# IoT_Shield_v1_2.net
KiCad netlist of a schematic drawn in EAGLE
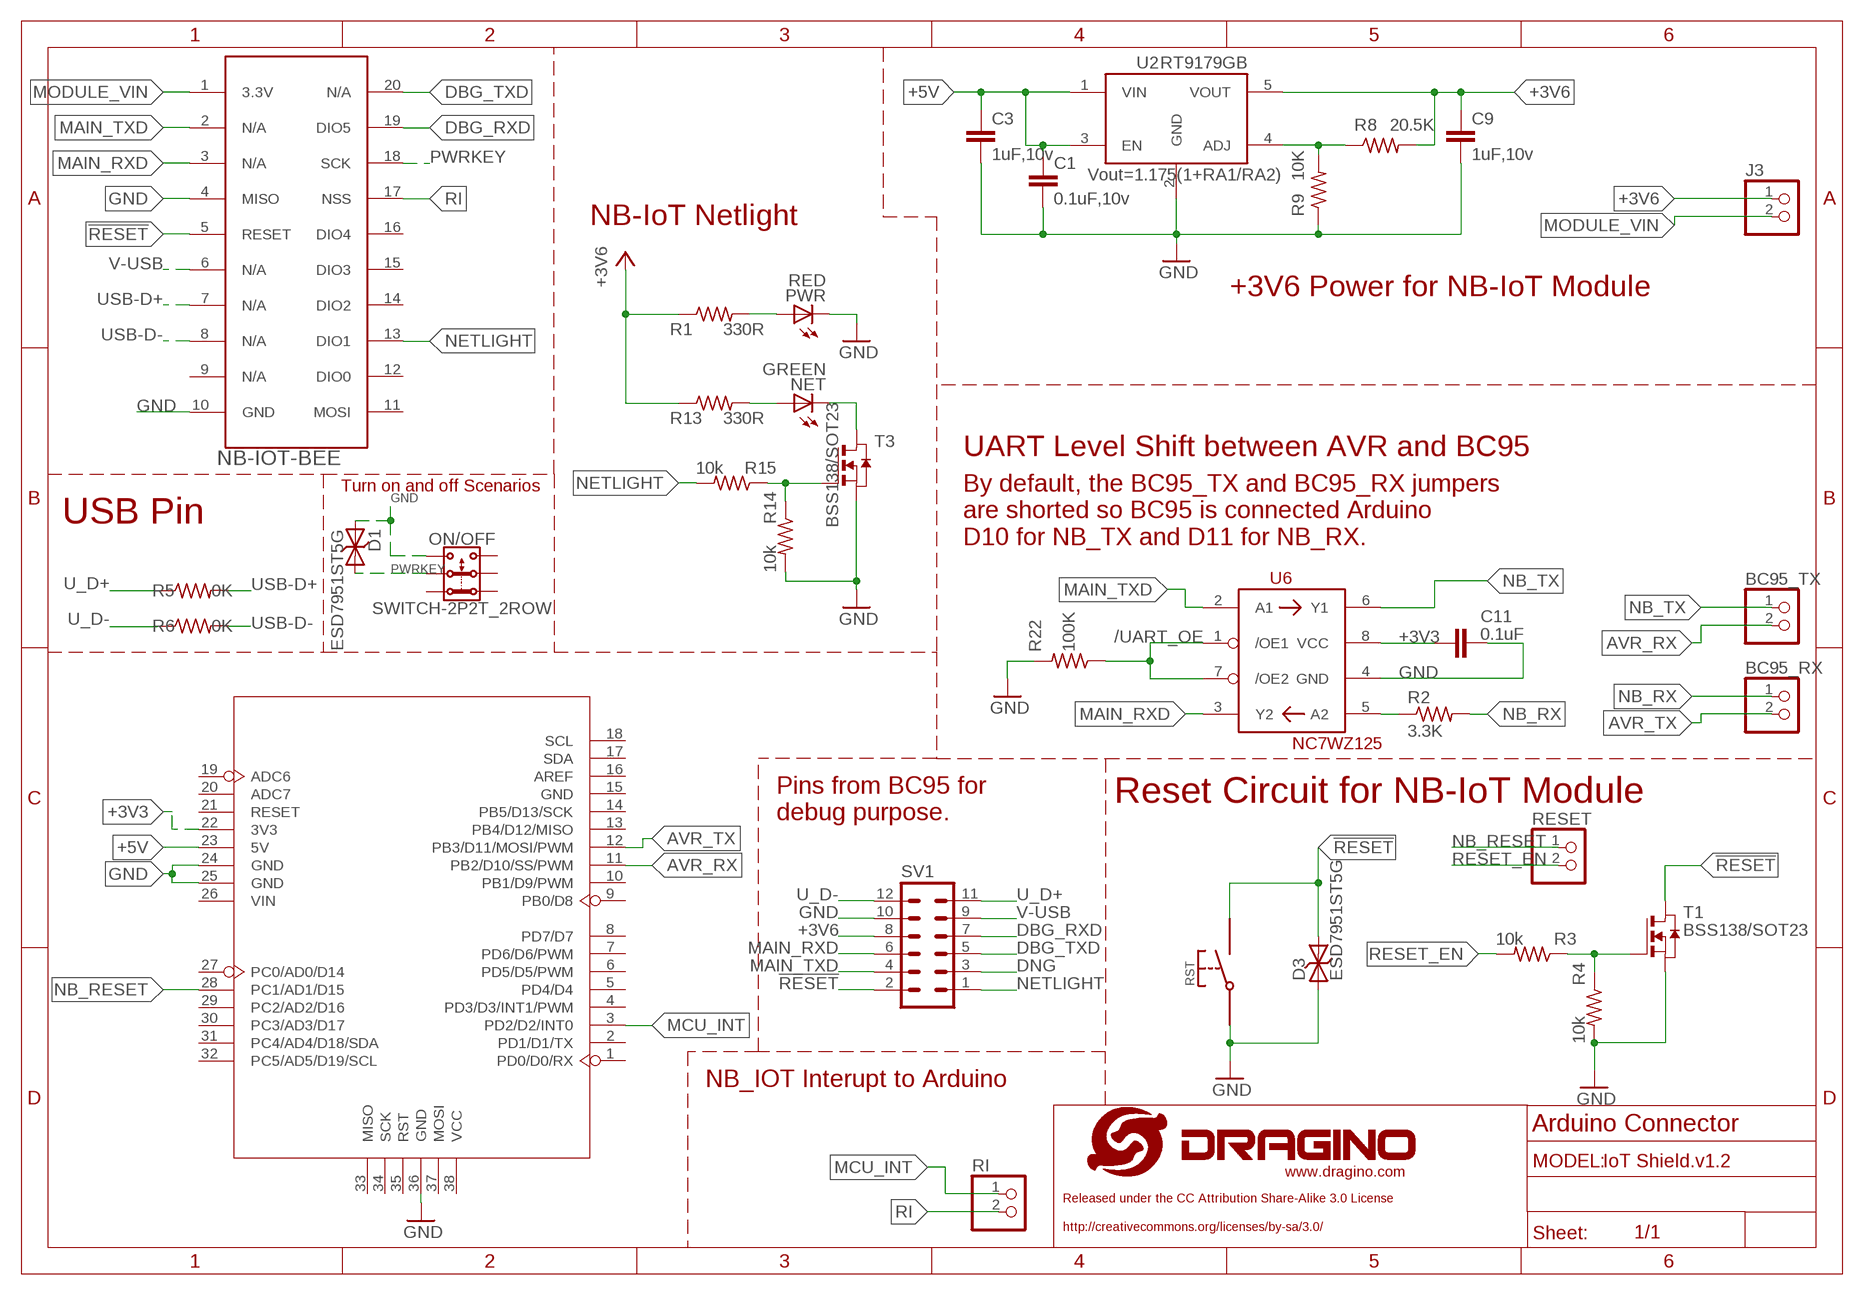
[diagram p0: schematic, sheet 1]

(export (version "E")
  (design (tool "Eeschema 10.0.6"))
  (components
    (comp (ref "BC95_RX")
      (value "PINHD-1X2")
      (footprint "eagle-import:1X02")
      (libsource (lib "eagle-import") (part "PINHD-1X2"))
    )
    (comp (ref "BC95_TX")
      (value "PINHD-1X2")
      (footprint "eagle-import:1X02")
      (libsource (lib "eagle-import") (part "PINHD-1X2"))
    )
    (comp (ref "C1")
      (value "0.1uF,10v")
      (footprint "eagle-import:C0402")
      (libsource (lib "eagle-import") (part "C-EUC0402"))
    )
    (comp (ref "C3")
      (value "1uF,10v")
      (footprint "eagle-import:C0402")
      (libsource (lib "eagle-import") (part "C-EUC0402"))
    )
    (comp (ref "C9")
      (value "1uF,10v")
      (footprint "eagle-import:C0402")
      (libsource (lib "eagle-import") (part "C-EUC0402"))
    )
    (comp (ref "C11")
      (value "0.1uF")
      (footprint "eagle-import:C0402")
      (libsource (lib "eagle-import") (part "C-EUC0402"))
    )
    (comp (ref "D1")
      (value "ESD7951ST5G")
      (footprint "eagle-import:SOD−923")
      (libsource (lib "eagle-import") (part "TVSSOD−923"))
    )
    (comp (ref "D3")
      (value "ESD7951ST5G")
      (footprint "eagle-import:SOD−923")
      (libsource (lib "eagle-import") (part "TVSSOD−923"))
    )
    (comp (ref "IOT-BEE")
      (value "NB-IOT-BEE")
      (footprint "eagle-import:LORA")
      (libsource (lib "eagle-import") (part "LORAHAT_S"))
    )
    (comp (ref "J3")
      (value "PINHD-1X2")
      (footprint "eagle-import:1X02")
      (libsource (lib "eagle-import") (part "PINHD-1X2"))
    )
    (comp (ref "NET")
      (value "GREEN")
      (footprint "eagle-import:CHIP-LED0603")
      (libsource (lib "eagle-import") (part "LEDCHIP-LED0603"))
    )
    (comp (ref "ON/OFF")
      (value "SWITCH-2P2T_2ROW")
      (footprint "eagle-import:KFT7.0-7X7")
      (libsource (lib "eagle-import") (part "SWITCH-2P2T_2ROW"))
    )
    (comp (ref "PWR")
      (value "RED")
      (footprint "eagle-import:CHIP-LED0603")
      (libsource (lib "eagle-import") (part "LEDCHIP-LED0603"))
    )
    (comp (ref "R1")
      (value "330R")
      (footprint "eagle-import:R0402")
      (libsource (lib "eagle-import") (part "R-US_R0402"))
    )
    (comp (ref "R2")
      (value "3.3K")
      (footprint "eagle-import:R0402")
      (libsource (lib "eagle-import") (part "R-US_R0402"))
    )
    (comp (ref "R3")
      (value "10k")
      (footprint "eagle-import:R0402")
      (libsource (lib "eagle-import") (part "R-US_R0402"))
    )
    (comp (ref "R4")
      (value "10k")
      (footprint "eagle-import:R0402")
      (libsource (lib "eagle-import") (part "R-US_R0402"))
    )
    (comp (ref "R5")
      (value "0K")
      (footprint "eagle-import:R0402")
      (libsource (lib "eagle-import") (part "R-US_R0402"))
    )
    (comp (ref "R6")
      (value "0K")
      (footprint "eagle-import:R0402")
      (libsource (lib "eagle-import") (part "R-US_R0402"))
    )
    (comp (ref "R8")
      (value "20.5K")
      (footprint "eagle-import:R0402")
      (libsource (lib "eagle-import") (part "R-US_R0402"))
    )
    (comp (ref "R9")
      (value "10K")
      (footprint "eagle-import:R0402")
      (libsource (lib "eagle-import") (part "R-US_R0402"))
    )
    (comp (ref "R13")
      (value "330R")
      (footprint "eagle-import:R0402")
      (libsource (lib "eagle-import") (part "R-US_R0402"))
    )
    (comp (ref "R14")
      (value "10k")
      (footprint "eagle-import:R0402")
      (libsource (lib "eagle-import") (part "R-US_R0402"))
    )
    (comp (ref "R15")
      (value "10k")
      (footprint "eagle-import:R0402")
      (libsource (lib "eagle-import") (part "R-US_R0402"))
    )
    (comp (ref "R22")
      (value "100K")
      (footprint "eagle-import:R0402")
      (libsource (lib "eagle-import") (part "R-US_R0402"))
    )
    (comp (ref "RESET")
      (value "PINHD-1X2")
      (footprint "eagle-import:1X02")
      (libsource (lib "eagle-import") (part "PINHD-1X2"))
    )
    (comp (ref "RI")
      (value "PINHD-1X2")
      (footprint "eagle-import:1X02")
      (libsource (lib "eagle-import") (part "PINHD-1X2"))
    )
    (comp (ref "RST")
      (value "SWITCHTS-16")
      (footprint "eagle-import:TS-016")
      (libsource (lib "eagle-import") (part "SWITCHTS-16"))
    )
    (comp (ref "SV1")
      (value "MA06-2")
      (footprint "eagle-import:MA06-2")
      (libsource (lib "eagle-import") (part "MA06-2"))
    )
    (comp (ref "T1")
      (value "BSS138/SOT23")
      (footprint "eagle-import:SOT-23")
      (libsource (lib "eagle-import") (part "NMOSFET-SOT23"))
    )
    (comp (ref "T3")
      (value "BSS138/SOT23")
      (footprint "eagle-import:SOT-23")
      (libsource (lib "eagle-import") (part "NMOSFET-SOT23"))
    )
    (comp (ref "U$1")
      (value "LOGO-NEW")
      (footprint "eagle-import:LOGO-SILK-NEW")
      (libsource (lib "eagle-import") (part "LOGO-NEW"))
    )
    (comp (ref "U2")
      (value "RT9179GB")
      (footprint "eagle-import:SOT23-5")
      (libsource (lib "eagle-import") (part "RT9179"))
    )
    (comp (ref "U5")
      (value "MOUDLE_ARDUINO-38PMOUDLE_ARDUINO-38P_L")
      (footprint "eagle-import:MOUDLE_ARDUINO-38P_L")
      (libsource (lib "eagle-import") (part "MOUDLE_ARDUINO-38PMOUDLE_ARDUINO-38P_L"))
    )
    (comp (ref "U6")
      (value "NC7WZ125")
      (footprint "eagle-import:US8")
      (libsource (lib "eagle-import") (part "NC7WZ125"))
    )
  )
  (nets
    (net (code "1") (name "+3V3") (class "Default")
      (node (ref "C11") (pin "2") (pinfunction "2_2") (pintype "passive"))
      (node (ref "U5") (pin "22") (pinfunction "3V3_22") (pintype "bidirectional"))
      (node (ref "U6") (pin "8") (pinfunction "VCC_8") (pintype "power_in"))
    )
    (net (code "2") (name "+3V6") (class "Default")
      (node (ref "C9") (pin "1") (pinfunction "1_1") (pintype "passive"))
      (node (ref "J3") (pin "1") (pinfunction "1_1") (pintype "passive"))
      (node (ref "R1") (pin "1") (pinfunction "1_1") (pintype "passive"))
      (node (ref "R13") (pin "1") (pinfunction "1_1") (pintype "passive"))
      (node (ref "R8") (pin "2") (pinfunction "2_2") (pintype "passive"))
      (node (ref "SV1") (pin "8") (pinfunction "8_8") (pintype "passive"))
      (node (ref "U2") (pin "5") (pinfunction "VOUT_5") (pintype "bidirectional"))
    )
    (net (code "3") (name "+5V") (class "Default")
      (node (ref "C1") (pin "1") (pinfunction "1_1") (pintype "passive"))
      (node (ref "C3") (pin "1") (pinfunction "1_1") (pintype "passive"))
      (node (ref "U2") (pin "1") (pinfunction "VIN_1") (pintype "bidirectional"))
      (node (ref "U2") (pin "3") (pinfunction "EN_3") (pintype "bidirectional"))
      (node (ref "U5") (pin "23") (pinfunction "5V_23") (pintype "bidirectional"))
    )
    (net (code "4") (name "/DNG") (class "Default")
      (node (ref "SV1") (pin "3") (pinfunction "3_3") (pintype "passive"))
    )
    (net (code "5") (name "/PWRKEY") (class "Default")
      (node (ref "D1") (pin "P$2") (pinfunction "2_P$2") (pintype "passive"))
      (node (ref "IOT-BEE") (pin "18") (pinfunction "SCK_18") (pintype "bidirectional"))
      (node (ref "ON/OFF") (pin "2.1") (pinfunction "2.1_2.1") (pintype "passive"))
    )
    (net (code "6") (name "/USB-D+") (class "Default")
      (node (ref "IOT-BEE") (pin "7") (pinfunction "N/A_7") (pintype "bidirectional"))
      (node (ref "R5") (pin "2") (pinfunction "2_2") (pintype "passive"))
    )
    (net (code "7") (name "/USB-D-") (class "Default")
      (node (ref "IOT-BEE") (pin "8") (pinfunction "N/A_8") (pintype "bidirectional"))
      (node (ref "R6") (pin "2") (pinfunction "2_2") (pintype "passive"))
    )
    (net (code "8") (name "/U_D+") (class "Default")
      (node (ref "R5") (pin "1") (pinfunction "1_1") (pintype "passive"))
      (node (ref "SV1") (pin "11") (pinfunction "11_11") (pintype "passive"))
    )
    (net (code "9") (name "/U_D-") (class "Default")
      (node (ref "R6") (pin "1") (pinfunction "1_1") (pintype "passive"))
      (node (ref "SV1") (pin "12") (pinfunction "12_12") (pintype "passive"))
    )
    (net (code "10") (name "/V-USB") (class "Default")
      (node (ref "IOT-BEE") (pin "6") (pinfunction "N/A_6") (pintype "bidirectional"))
      (node (ref "SV1") (pin "9") (pinfunction "9_9") (pintype "passive"))
    )
    (net (code "11") (name "/{slash}UART_OE") (class "Default")
      (node (ref "R22") (pin "1") (pinfunction "1_1") (pintype "passive"))
      (node (ref "U6") (pin "1") (pinfunction "/OE1_1") (pintype "input"))
      (node (ref "U6") (pin "7") (pinfunction "/OE2_7") (pintype "input"))
    )
    (net (code "12") (name "/~{RESET}") (class "Default")
      (node (ref "D3") (pin "P$2") (pinfunction "2_P$2") (pintype "passive"))
      (node (ref "IOT-BEE") (pin "5") (pinfunction "RESET_5") (pintype "bidirectional"))
      (node (ref "RST") (pin "P$2") (pinfunction "P$2_P$2") (pintype "bidirectional"))
      (node (ref "SV1") (pin "2") (pinfunction "2_2") (pintype "passive"))
      (node (ref "T1") (pin "1") (pinfunction "D_1") (pintype "passive"))
    )
    (net (code "13") (name "AVR_RX") (class "Default")
      (node (ref "BC95_TX") (pin "2") (pinfunction "2_2") (pintype "passive"))
      (node (ref "U5") (pin "11") (pinfunction "PB2/D10/SS/PWM_11") (pintype "bidirectional"))
    )
    (net (code "14") (name "AVR_TX") (class "Default")
      (node (ref "BC95_RX") (pin "2") (pinfunction "2_2") (pintype "passive"))
      (node (ref "U5") (pin "12") (pinfunction "PB3/D11/MOSI/PWM_12") (pintype "bidirectional"))
    )
    (net (code "15") (name "DBG_RXD") (class "Default")
      (node (ref "IOT-BEE") (pin "19") (pinfunction "DIO5_19") (pintype "bidirectional"))
      (node (ref "SV1") (pin "7") (pinfunction "7_7") (pintype "passive"))
    )
    (net (code "16") (name "DBG_TXD") (class "Default")
      (node (ref "IOT-BEE") (pin "20") (pinfunction "N/A_20") (pintype "bidirectional"))
      (node (ref "SV1") (pin "5") (pinfunction "5_5") (pintype "passive"))
    )
    (net (code "17") (name "GND") (class "Default")
      (node (ref "C1") (pin "2") (pinfunction "2_2") (pintype "passive"))
      (node (ref "C11") (pin "1") (pinfunction "1_1") (pintype "passive"))
      (node (ref "C3") (pin "2") (pinfunction "2_2") (pintype "passive"))
      (node (ref "C9") (pin "2") (pinfunction "2_2") (pintype "passive"))
      (node (ref "D1") (pin "P$1") (pinfunction "1_P$1") (pintype "passive"))
      (node (ref "D3") (pin "P$1") (pinfunction "1_P$1") (pintype "passive"))
      (node (ref "IOT-BEE") (pin "10") (pinfunction "GND_10") (pintype "bidirectional"))
      (node (ref "IOT-BEE") (pin "4") (pinfunction "MISO_4") (pintype "bidirectional"))
      (node (ref "ON/OFF") (pin "3.1") (pinfunction "3.1_3.1") (pintype "passive"))
      (node (ref "PWR") (pin "C") (pinfunction "C_C") (pintype "passive"))
      (node (ref "R14") (pin "2") (pinfunction "2_2") (pintype "passive"))
      (node (ref "R22") (pin "2") (pinfunction "2_2") (pintype "passive"))
      (node (ref "R4") (pin "2") (pinfunction "2_2") (pintype "passive"))
      (node (ref "R9") (pin "1") (pinfunction "1_1") (pintype "passive"))
      (node (ref "RST") (pin "P$1") (pinfunction "P$1_P$1") (pintype "bidirectional"))
      (node (ref "SV1") (pin "10") (pinfunction "10_10") (pintype "passive"))
      (node (ref "T1") (pin "2") (pinfunction "S_2") (pintype "passive"))
      (node (ref "T3") (pin "2") (pinfunction "S_2") (pintype "passive"))
      (node (ref "U2") (pin "2") (pinfunction "GND_2") (pintype "bidirectional"))
      (node (ref "U5") (pin "24") (pinfunction "GND_24") (pintype "bidirectional"))
      (node (ref "U5") (pin "25") (pinfunction "GND_25") (pintype "bidirectional"))
      (node (ref "U5") (pin "36") (pinfunction "GND_36") (pintype "bidirectional"))
      (node (ref "U6") (pin "4") (pinfunction "GND_4") (pintype "power_in"))
    )
    (net (code "18") (name "MAIN_RXD") (class "Default")
      (node (ref "IOT-BEE") (pin "3") (pinfunction "N/A_3") (pintype "bidirectional"))
      (node (ref "SV1") (pin "6") (pinfunction "6_6") (pintype "passive"))
      (node (ref "U6") (pin "3") (pinfunction "Y2_3") (pintype "output"))
    )
    (net (code "19") (name "MAIN_TXD") (class "Default")
      (node (ref "IOT-BEE") (pin "2") (pinfunction "N/A_2") (pintype "bidirectional"))
      (node (ref "SV1") (pin "4") (pinfunction "4_4") (pintype "passive"))
      (node (ref "U6") (pin "2") (pinfunction "A1_2") (pintype "input"))
    )
    (net (code "20") (name "MCU_INT") (class "Default")
      (node (ref "RI") (pin "1") (pinfunction "1_1") (pintype "passive"))
      (node (ref "U5") (pin "3") (pinfunction "PD2/D2/INT0_3") (pintype "bidirectional"))
    )
    (net (code "21") (name "MODULE_VIN") (class "Default")
      (node (ref "IOT-BEE") (pin "1") (pinfunction "3.3V_1") (pintype "bidirectional"))
      (node (ref "J3") (pin "2") (pinfunction "2_2") (pintype "passive"))
    )
    (net (code "22") (name "NB_RESET") (class "Default")
      (node (ref "RESET") (pin "1") (pinfunction "1_1") (pintype "passive"))
      (node (ref "U5") (pin "28") (pinfunction "PC1/AD1/D15_28") (pintype "bidirectional"))
    )
    (net (code "23") (name "NB_RX") (class "Default")
      (node (ref "BC95_RX") (pin "1") (pinfunction "1_1") (pintype "passive"))
      (node (ref "R2") (pin "2") (pinfunction "2_2") (pintype "passive"))
    )
    (net (code "24") (name "NB_TX") (class "Default")
      (node (ref "BC95_TX") (pin "1") (pinfunction "1_1") (pintype "passive"))
      (node (ref "U6") (pin "6") (pinfunction "Y1_6") (pintype "output"))
    )
    (net (code "25") (name "NETLIGHT") (class "Default")
      (node (ref "IOT-BEE") (pin "13") (pinfunction "DIO1_13") (pintype "bidirectional"))
      (node (ref "R15") (pin "2") (pinfunction "2_2") (pintype "passive"))
      (node (ref "SV1") (pin "1") (pinfunction "1_1") (pintype "passive"))
    )
    (net (code "26") (name "Net-(NET-PadA)") (class "Default")
      (node (ref "NET") (pin "A") (pinfunction "A_A") (pintype "passive"))
      (node (ref "R13") (pin "2") (pinfunction "2_2") (pintype "passive"))
    )
    (net (code "27") (name "Net-(PWR-PadA)") (class "Default")
      (node (ref "PWR") (pin "A") (pinfunction "A_A") (pintype "passive"))
      (node (ref "R1") (pin "2") (pinfunction "2_2") (pintype "passive"))
    )
    (net (code "28") (name "Net-(T1-G)") (class "Default")
      (node (ref "R3") (pin "1") (pinfunction "1_1") (pintype "passive"))
      (node (ref "R4") (pin "1") (pinfunction "1_1") (pintype "passive"))
      (node (ref "T1") (pin "3") (pinfunction "G_3") (pintype "passive"))
    )
    (net (code "29") (name "Net-(T3-D)") (class "Default")
      (node (ref "NET") (pin "C") (pinfunction "C_C") (pintype "passive"))
      (node (ref "T3") (pin "1") (pinfunction "D_1") (pintype "passive"))
    )
    (net (code "30") (name "Net-(T3-G)") (class "Default")
      (node (ref "R14") (pin "1") (pinfunction "1_1") (pintype "passive"))
      (node (ref "R15") (pin "1") (pinfunction "1_1") (pintype "passive"))
      (node (ref "T3") (pin "3") (pinfunction "G_3") (pintype "passive"))
    )
    (net (code "31") (name "Net-(U2-ADJ)") (class "Default")
      (node (ref "R8") (pin "1") (pinfunction "1_1") (pintype "passive"))
      (node (ref "R9") (pin "2") (pinfunction "2_2") (pintype "passive"))
      (node (ref "U2") (pin "4") (pinfunction "ADJ_4") (pintype "bidirectional"))
    )
    (net (code "32") (name "Net-(U6-A2)") (class "Default")
      (node (ref "R2") (pin "1") (pinfunction "1_1") (pintype "passive"))
      (node (ref "U6") (pin "5") (pinfunction "A2_5") (pintype "input"))
    )
    (net (code "33") (name "RESET_EN") (class "Default")
      (node (ref "R3") (pin "2") (pinfunction "2_2") (pintype "passive"))
      (node (ref "RESET") (pin "2") (pinfunction "2_2") (pintype "passive"))
    )
    (net (code "34") (name "RI") (class "Default")
      (node (ref "IOT-BEE") (pin "17") (pinfunction "NSS_17") (pintype "bidirectional"))
      (node (ref "RI") (pin "2") (pinfunction "2_2") (pintype "passive"))
    )
    (net (code "35") (name "unconnected-(IOT-BEE-DIO0-Pad12)") (class "Default")
      (node (ref "IOT-BEE") (pin "12") (pinfunction "DIO0_12") (pintype "bidirectional"))
    )
    (net (code "36") (name "unconnected-(IOT-BEE-DIO2-Pad14)") (class "Default")
      (node (ref "IOT-BEE") (pin "14") (pinfunction "DIO2_14") (pintype "bidirectional"))
    )
    (net (code "37") (name "unconnected-(IOT-BEE-DIO3-Pad15)") (class "Default")
      (node (ref "IOT-BEE") (pin "15") (pinfunction "DIO3_15") (pintype "bidirectional"))
    )
    (net (code "38") (name "unconnected-(IOT-BEE-DIO4-Pad16)") (class "Default")
      (node (ref "IOT-BEE") (pin "16") (pinfunction "DIO4_16") (pintype "bidirectional"))
    )
    (net (code "39") (name "unconnected-(IOT-BEE-MOSI-Pad11)") (class "Default")
      (node (ref "IOT-BEE") (pin "11") (pinfunction "MOSI_11") (pintype "bidirectional"))
    )
    (net (code "40") (name "unconnected-(IOT-BEE-N{slash}A-Pad9)") (class "Default")
      (node (ref "IOT-BEE") (pin "9") (pinfunction "N/A_9") (pintype "bidirectional"))
    )
    (net (code "41") (name "unconnected-(ON/OFF-Pad1.1)") (class "Default")
      (node (ref "ON/OFF") (pin "1.1") (pinfunction "1.1_1.1") (pintype "passive"))
    )
    (net (code "42") (name "unconnected-(ON/OFF-Pad1.2)") (class "Default")
      (node (ref "ON/OFF") (pin "1.2") (pinfunction "1.2_1.2") (pintype "passive"))
    )
    (net (code "43") (name "unconnected-(ON/OFF-Pad2.2)") (class "Default")
      (node (ref "ON/OFF") (pin "2.2") (pinfunction "2.2_2.2") (pintype "passive"))
    )
    (net (code "44") (name "unconnected-(ON/OFF-Pad3.2)") (class "Default")
      (node (ref "ON/OFF") (pin "3.2") (pinfunction "3.2_3.2") (pintype "passive"))
    )
    (net (code "45") (name "unconnected-(U5-ADC6-Pad19)") (class "Default")
      (node (ref "U5") (pin "19") (pinfunction "ADC6_19") (pintype "bidirectional"))
    )
    (net (code "46") (name "unconnected-(U5-ADC7-Pad20)") (class "Default")
      (node (ref "U5") (pin "20") (pinfunction "ADC7_20") (pintype "bidirectional"))
    )
    (net (code "47") (name "unconnected-(U5-AREF-Pad16)") (class "Default")
      (node (ref "U5") (pin "16") (pinfunction "AREF_16") (pintype "bidirectional"))
    )
    (net (code "48") (name "unconnected-(U5-GND-Pad15)") (class "Default")
      (node (ref "U5") (pin "15") (pinfunction "GND_15") (pintype "bidirectional"))
    )
    (net (code "49") (name "unconnected-(U5-MISO-Pad33)") (class "Default")
      (node (ref "U5") (pin "33") (pinfunction "MISO_33") (pintype "bidirectional"))
    )
    (net (code "50") (name "unconnected-(U5-MOSI-Pad37)") (class "Default")
      (node (ref "U5") (pin "37") (pinfunction "MOSI_37") (pintype "bidirectional"))
    )
    (net (code "51") (name "unconnected-(U5-PB0{slash}D8-Pad9)") (class "Default")
      (node (ref "U5") (pin "9") (pinfunction "PB0/D8_9") (pintype "bidirectional"))
    )
    (net (code "52") (name "unconnected-(U5-PB1{slash}D9{slash}PWM-Pad10)") (class "Default")
      (node (ref "U5") (pin "10") (pinfunction "PB1/D9/PWM_10") (pintype "bidirectional"))
    )
    (net (code "53") (name "unconnected-(U5-PB4{slash}D12{slash}MISO-Pad13)") (class "Default")
      (node (ref "U5") (pin "13") (pinfunction "PB4/D12/MISO_13") (pintype "bidirectional"))
    )
    (net (code "54") (name "unconnected-(U5-PB5{slash}D13{slash}SCK-Pad14)") (class "Default")
      (node (ref "U5") (pin "14") (pinfunction "PB5/D13/SCK_14") (pintype "bidirectional"))
    )
    (net (code "55") (name "unconnected-(U5-PC0{slash}AD0{slash}D14-Pad27)") (class "Default")
      (node (ref "U5") (pin "27") (pinfunction "PC0/AD0/D14_27") (pintype "bidirectional"))
    )
    (net (code "56") (name "unconnected-(U5-PC2{slash}AD2{slash}D16-Pad29)") (class "Default")
      (node (ref "U5") (pin "29") (pinfunction "PC2/AD2/D16_29") (pintype "bidirectional"))
    )
    (net (code "57") (name "unconnected-(U5-PC3{slash}AD3{slash}D17-Pad30)") (class "Default")
      (node (ref "U5") (pin "30") (pinfunction "PC3/AD3/D17_30") (pintype "bidirectional"))
    )
    (net (code "58") (name "unconnected-(U5-PC4{slash}AD4{slash}D18{slash}SDA-Pad31)") (class "Default")
      (node (ref "U5") (pin "31") (pinfunction "PC4/AD4/D18/SDA_31") (pintype "bidirectional"))
    )
    (net (code "59") (name "unconnected-(U5-PC5{slash}AD5{slash}D19{slash}SCL-Pad32)") (class "Default")
      (node (ref "U5") (pin "32") (pinfunction "PC5/AD5/D19/SCL_32") (pintype "bidirectional"))
    )
    (net (code "60") (name "unconnected-(U5-PD0{slash}D0{slash}RX-Pad1)") (class "Default")
      (node (ref "U5") (pin "1") (pinfunction "PD0/D0/RX_1") (pintype "bidirectional"))
    )
    (net (code "61") (name "unconnected-(U5-PD1{slash}D1{slash}TX-Pad2)") (class "Default")
      (node (ref "U5") (pin "2") (pinfunction "PD1/D1/TX_2") (pintype "bidirectional"))
    )
    (net (code "62") (name "unconnected-(U5-PD3{slash}D3{slash}INT1{slash}PWM-Pad4)") (class "Default")
      (node (ref "U5") (pin "4") (pinfunction "PD3/D3/INT1/PWM_4") (pintype "bidirectional"))
    )
    (net (code "63") (name "unconnected-(U5-PD4{slash}D4-Pad5)") (class "Default")
      (node (ref "U5") (pin "5") (pinfunction "PD4/D4_5") (pintype "bidirectional"))
    )
    (net (code "64") (name "unconnected-(U5-PD5{slash}D5{slash}PWM-Pad6)") (class "Default")
      (node (ref "U5") (pin "6") (pinfunction "PD5/D5/PWM_6") (pintype "bidirectional"))
    )
    (net (code "65") (name "unconnected-(U5-PD6{slash}D6{slash}PWM-Pad7)") (class "Default")
      (node (ref "U5") (pin "7") (pinfunction "PD6/D6/PWM_7") (pintype "bidirectional"))
    )
    (net (code "66") (name "unconnected-(U5-PD7{slash}D7-Pad8)") (class "Default")
      (node (ref "U5") (pin "8") (pinfunction "PD7/D7_8") (pintype "bidirectional"))
    )
    (net (code "67") (name "unconnected-(U5-RESET-Pad21)") (class "Default")
      (node (ref "U5") (pin "21") (pinfunction "RESET_21") (pintype "bidirectional"))
    )
    (net (code "68") (name "unconnected-(U5-RST-Pad35)") (class "Default")
      (node (ref "U5") (pin "35") (pinfunction "RST_35") (pintype "bidirectional"))
    )
    (net (code "69") (name "unconnected-(U5-SCK-Pad34)") (class "Default")
      (node (ref "U5") (pin "34") (pinfunction "SCK_34") (pintype "bidirectional"))
    )
    (net (code "70") (name "unconnected-(U5-SCL-Pad18)") (class "Default")
      (node (ref "U5") (pin "18") (pinfunction "SCL_18") (pintype "bidirectional"))
    )
    (net (code "71") (name "unconnected-(U5-SDA-Pad17)") (class "Default")
      (node (ref "U5") (pin "17") (pinfunction "SDA_17") (pintype "bidirectional"))
    )
    (net (code "72") (name "unconnected-(U5-VCC-Pad38)") (class "Default")
      (node (ref "U5") (pin "38") (pinfunction "VCC_38") (pintype "bidirectional"))
    )
    (net (code "73") (name "unconnected-(U5-VIN-Pad26)") (class "Default")
      (node (ref "U5") (pin "26") (pinfunction "VIN_26") (pintype "bidirectional"))
    )
  )
)
